# INA288.net
KiCad netlist of a schematic drawn in Altium Designer
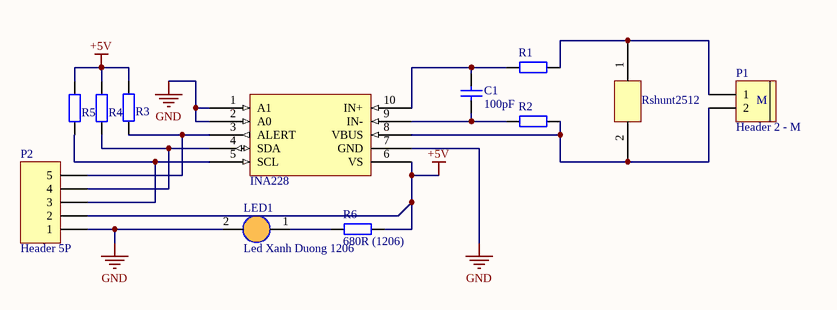
[diagram p0: INA288.SchDoc]

(export (version "E")
  (design (tool "Eeschema 10.0.6"))
  (components
    (comp (ref "C1")
      (value "100pF")
      (footprint "tu 1206")
      (description "Dán")
      (libsource (lib "SCH Chuan") (part "Tu 1206 100pF 50V 5%"))
    )
    (comp (ref "INA1") (value "INA228") (footprint "INA228") (libsource (lib "INA288") (part "INA228")))
    (comp (ref "LED1")
      (value "Led Xanh Duong 1206")
      (footprint "led 1206")
      (description "Dán")
      (libsource (lib "SCH Chuan") (part "Led 1206 Xanh Duong"))
    )
    (comp (ref "P1")
      (value "Header 2 - M")
      (footprint "Medium - Header 2")
      (description "Header, 2-Pin, Medium")
      (fields (field (name "PUBLISHER") "Altium Limited"))
      (libsource (lib "BYTECH_HW_LIB_2019") (part "Header 2 - M"))
    )
    (comp (ref "P2")
      (value "Header 5P")
      (footprint "HDR1X5")
      (description "Header, 5 Pin Pitch 2.54mm")
      (fields (field (name "MPN") "S1012EC-40-ND"))
      (libsource (lib "BYTECH_HW_LIB_2019") (part "Header 5x1"))
    )
    (comp (ref "R1")
      (value "1R (1206)")
      (footprint "TRO 1206")
      (description "Dán")
      (libsource (lib "SCH Chuan") (part "Tro 1206 5% 1R"))
    )
    (comp (ref "R2")
      (value "1R (1206)")
      (footprint "TRO 1206")
      (description "Dán")
      (libsource (lib "SCH Chuan") (part "Tro 1206 5% 1R"))
    )
    (comp (ref "R3")
      (value "10k (1206-1%)")
      (footprint "TRO 1206")
      (description "Dán")
      (libsource (lib "SCH Chuan") (part "Tro 1206 1% 10k"))
    )
    (comp (ref "R4")
      (value "10k (1206-1%)")
      (footprint "TRO 1206")
      (description "Dán")
      (libsource (lib "SCH Chuan") (part "Tro 1206 1% 10k"))
    )
    (comp (ref "R5")
      (value "10k (1206-1%)")
      (footprint "TRO 1206")
      (description "Dán")
      (libsource (lib "SCH Chuan") (part "Tro 1206 1% 10k"))
    )
    (comp (ref "R6")
      (value "680R (1206)")
      (footprint "TRO 1206")
      (description "Dán")
      (libsource (lib "SCH Chuan") (part "Tro 1206 5% 680R"))
    )
    (comp (ref "Rshunt1")
      (value "Rshunt2512")
      (footprint "Rshunt2512")
      (libsource (lib "Rshunt2512") (part "Rshunt2512"))
    )
  )
  (nets
    (net (code "1") (name "+5V") (class "Default")
      (node (ref "INA1") (pin "6") (pinfunction "VS_6") (pintype "power_in"))
      (node (ref "P2") (pin "2") (pinfunction "2_2") (pintype "passive"))
      (node (ref "R3") (pin "1") (pinfunction "1_1") (pintype "passive"))
      (node (ref "R4") (pin "2") (pinfunction "2_2") (pintype "passive"))
      (node (ref "R5") (pin "2") (pinfunction "2_2") (pintype "passive"))
      (node (ref "R6") (pin "2") (pinfunction "2_2") (pintype "passive"))
    )
    (net (code "2") (name "GND") (class "Default")
      (node (ref "INA1") (pin "1") (pinfunction "A1_1") (pintype "input"))
      (node (ref "INA1") (pin "2") (pinfunction "A0_2") (pintype "input"))
      (node (ref "INA1") (pin "7") (pinfunction "GND_7") (pintype "power_in"))
      (node (ref "LED1") (pin "2") (pinfunction "K_2") (pintype "passive"))
      (node (ref "P2") (pin "1") (pinfunction "1_1") (pintype "passive"))
    )
    (net (code "3") (name "Net-(INA1-ALERT)") (class "Default")
      (node (ref "INA1") (pin "3") (pinfunction "ALERT_3") (pintype "output"))
      (node (ref "P2") (pin "5") (pinfunction "5_5") (pintype "passive"))
      (node (ref "R3") (pin "2") (pinfunction "2_2") (pintype "passive"))
    )
    (net (code "4") (name "Net-(INA1-IN+)") (class "Default")
      (node (ref "C1") (pin "1") (pinfunction "1_1") (pintype "passive"))
      (node (ref "INA1") (pin "10") (pinfunction "IN+_10") (pintype "input"))
      (node (ref "R1") (pin "1") (pinfunction "1_1") (pintype "passive"))
    )
    (net (code "5") (name "Net-(INA1-IN-)") (class "Default")
      (node (ref "C1") (pin "2") (pinfunction "2_2") (pintype "passive"))
      (node (ref "INA1") (pin "9") (pinfunction "IN-_9") (pintype "input"))
      (node (ref "R2") (pin "1") (pinfunction "1_1") (pintype "passive"))
    )
    (net (code "6") (name "Net-(INA1-SCL)") (class "Default")
      (node (ref "INA1") (pin "5") (pinfunction "SCL_5") (pintype "input"))
      (node (ref "P2") (pin "3") (pinfunction "3_3") (pintype "passive"))
      (node (ref "R5") (pin "1") (pinfunction "1_1") (pintype "passive"))
    )
    (net (code "7") (name "Net-(INA1-SDA)") (class "Default")
      (node (ref "INA1") (pin "4") (pinfunction "SDA_4") (pintype "bidirectional"))
      (node (ref "P2") (pin "4") (pinfunction "4_4") (pintype "passive"))
      (node (ref "R4") (pin "1") (pinfunction "1_1") (pintype "passive"))
    )
    (net (code "8") (name "Net-(INA1-VBUS)") (class "Default")
      (node (ref "INA1") (pin "8") (pinfunction "VBUS_8") (pintype "input"))
      (node (ref "P1") (pin "2") (pinfunction "2_2") (pintype "passive"))
      (node (ref "R2") (pin "2") (pinfunction "2_2") (pintype "passive"))
      (node (ref "Rshunt1") (pin "2") (pintype "passive"))
    )
    (net (code "9") (name "Net-(LED1-A)") (class "Default")
      (node (ref "LED1") (pin "1") (pinfunction "A_1") (pintype "passive"))
      (node (ref "R6") (pin "1") (pinfunction "1_1") (pintype "passive"))
    )
    (net (code "10") (name "Net-(P1-Pad1)") (class "Default")
      (node (ref "P1") (pin "1") (pinfunction "1_1") (pintype "passive"))
      (node (ref "R1") (pin "2") (pinfunction "2_2") (pintype "passive"))
      (node (ref "Rshunt1") (pin "1") (pintype "passive"))
    )
  )
)
